# HB_main.net
KiCad netlist of a schematic drawn in Altium Designer
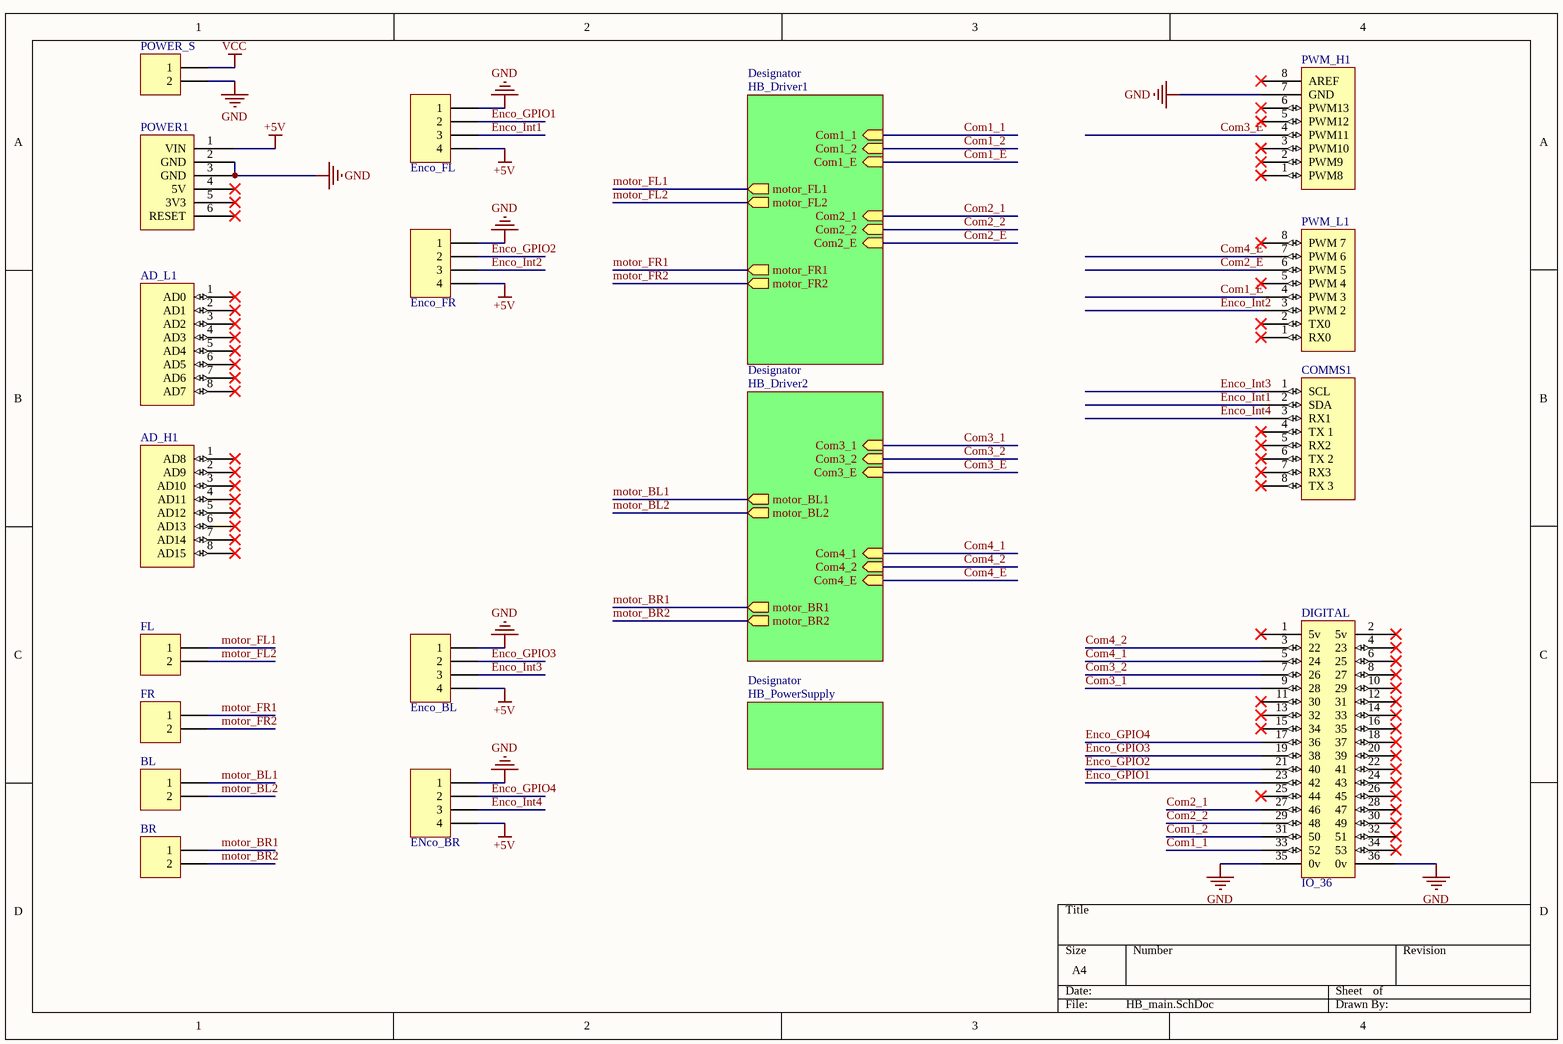
[diagram p0: HB_main.SchDoc]

(export (version "E")
  (design (tool "Eeschema 10.0.6"))
  (components
    (comp (ref "AD_H1")
      (value "AD_H")
      (footprint "Header 8x1 8.5mm")
      (description "Header, 8-Pin")
      (libsource (lib "HBLib") (part "AD_H"))
    )
    (comp (ref "AD_L1")
      (value "AD_L")
      (footprint "Header 8x1 8.5mm")
      (description "Header, 8-Pin")
      (libsource (lib "HBLib") (part "AD_L"))
    )
    (comp (ref "COMMS1")
      (value "Communication")
      (footprint "Header 8x1 8.5mm")
      (description "Header, 8-Pin")
      (libsource (lib "HBLib") (part "Communication"))
    )
    (comp (ref "DIGITAL")
      (value "IO_36")
      (footprint "HEADER 36X 8MM")
      (description "Header, 36-Pin")
      (libsource (lib "HBLib") (part "IO_36"))
    )
    (comp (ref "J3")
      (value "POWER_S")
      (footprint "Header_2")
      (description "Connecteur")
      (fields (field (name "DESIGNER") "ECAM 2005"))
      (libsource (lib "HBLib") (part "Connecteur 2"))
    )
    (comp (ref "J4")
      (value "FL")
      (footprint "Header_2")
      (description "Connecteur")
      (fields (field (name "DESIGNER") "ECAM 2005"))
      (libsource (lib "HBLib") (part "Connecteur 2"))
    )
    (comp (ref "J5")
      (value "FR")
      (footprint "Header_2")
      (description "Connecteur")
      (fields (field (name "DESIGNER") "ECAM 2005"))
      (libsource (lib "HBLib") (part "Connecteur 2"))
    )
    (comp (ref "J6")
      (value "BL")
      (footprint "Header_2")
      (description "Connecteur")
      (fields (field (name "DESIGNER") "ECAM 2005"))
      (libsource (lib "HBLib") (part "Connecteur 2"))
    )
    (comp (ref "J7")
      (value "BR")
      (footprint "Header_2")
      (description "Connecteur")
      (fields (field (name "DESIGNER") "ECAM 2005"))
      (libsource (lib "HBLib") (part "Connecteur 2"))
    )
    (comp (ref "P1")
      (value "Enco_FL")
      (footprint "MOLEX_22-27-2081")
      (description "Header, 4-Pin")
      (fields (field (name "PUBLISHER") "Altium Limited"))
      (libsource (lib "HBLib") (part "Header 4"))
    )
    (comp (ref "P2")
      (value "Enco_FR")
      (footprint "MOLEX_22-27-2081")
      (description "Header, 4-Pin")
      (fields (field (name "PUBLISHER") "Altium Limited"))
      (libsource (lib "HBLib") (part "Header 4"))
    )
    (comp (ref "P3")
      (value "Enco_BL")
      (footprint "MOLEX_22-27-2081")
      (description "Header, 4-Pin")
      (fields (field (name "PUBLISHER") "Altium Limited"))
      (libsource (lib "HBLib") (part "Header 4"))
    )
    (comp (ref "P4")
      (value "ENco_BR")
      (footprint "MOLEX_22-27-2081")
      (description "Header, 4-Pin")
      (fields (field (name "PUBLISHER") "Altium Limited"))
      (libsource (lib "HBLib") (part "Header 4"))
    )
    (comp (ref "POWER1")
      (value "POWER")
      (footprint "Header 6x1 8.5mm")
      (description "Header, 6-Pin")
      (libsource (lib "HBLib") (part "POWER"))
    )
    (comp (ref "PWM_H1")
      (value "PWM_H")
      (footprint "Header 8x1 8.5mm")
      (description "Header, 8-Pin")
      (libsource (lib "HBLib") (part "PWM_H"))
    )
    (comp (ref "PWM_L1")
      (value "PWM_L")
      (footprint "Header 8x1 8.5mm")
      (description "Header, 8-Pin")
      (libsource (lib "HBLib") (part "PWM_L"))
    )
  )
  (nets
    (net (code "1") (name "+5V") (class "Default")
      (node (ref "P1") (pin "4") (pinfunction "4_4") (pintype "passive"))
      (node (ref "P2") (pin "4") (pinfunction "4_4") (pintype "passive"))
      (node (ref "P3") (pin "4") (pinfunction "4_4") (pintype "passive"))
      (node (ref "P4") (pin "4") (pinfunction "4_4") (pintype "passive"))
      (node (ref "POWER1") (pin "1") (pinfunction "VIN_1") (pintype "power_in"))
    )
    (net (code "2") (name "/Com1_1") (class "Default")
      (node (ref "DIGITAL") (pin "33") (pinfunction "52_33") (pintype "bidirectional"))
    )
    (net (code "3") (name "/Com1_2") (class "Default")
      (node (ref "DIGITAL") (pin "31") (pinfunction "50_31") (pintype "bidirectional"))
    )
    (net (code "4") (name "/Com1_E") (class "Default")
      (node (ref "PWM_L1") (pin "4") (pinfunction "PWM_3_4") (pintype "bidirectional"))
    )
    (net (code "5") (name "/Com2_1") (class "Default")
      (node (ref "DIGITAL") (pin "27") (pinfunction "46_27") (pintype "bidirectional"))
    )
    (net (code "6") (name "/Com2_2") (class "Default")
      (node (ref "DIGITAL") (pin "29") (pinfunction "48_29") (pintype "bidirectional"))
    )
    (net (code "7") (name "/Com2_E") (class "Default")
      (node (ref "PWM_L1") (pin "6") (pinfunction "PWM_5_6") (pintype "bidirectional"))
    )
    (net (code "8") (name "/Com3_1") (class "Default")
      (node (ref "DIGITAL") (pin "9") (pinfunction "28_9") (pintype "bidirectional"))
    )
    (net (code "9") (name "/Com3_2") (class "Default")
      (node (ref "DIGITAL") (pin "7") (pinfunction "26_7") (pintype "bidirectional"))
    )
    (net (code "10") (name "/Com3_E") (class "Default")
      (node (ref "PWM_H1") (pin "4") (pinfunction "PWM11_4") (pintype "bidirectional"))
    )
    (net (code "11") (name "/Com4_1") (class "Default")
      (node (ref "DIGITAL") (pin "5") (pinfunction "24_5") (pintype "bidirectional"))
    )
    (net (code "12") (name "/Com4_2") (class "Default")
      (node (ref "DIGITAL") (pin "3") (pinfunction "22_3") (pintype "bidirectional"))
    )
    (net (code "13") (name "/Com4_E") (class "Default")
      (node (ref "PWM_L1") (pin "7") (pinfunction "PWM_6_7") (pintype "bidirectional"))
    )
    (net (code "14") (name "/Enco_GPIO1") (class "Default")
      (node (ref "DIGITAL") (pin "23") (pinfunction "42_23") (pintype "bidirectional"))
      (node (ref "P1") (pin "2") (pinfunction "2_2") (pintype "passive"))
    )
    (net (code "15") (name "/Enco_GPIO2") (class "Default")
      (node (ref "DIGITAL") (pin "21") (pinfunction "40_21") (pintype "bidirectional"))
      (node (ref "P2") (pin "2") (pinfunction "2_2") (pintype "passive"))
    )
    (net (code "16") (name "/Enco_GPIO3") (class "Default")
      (node (ref "DIGITAL") (pin "19") (pinfunction "38_19") (pintype "bidirectional"))
      (node (ref "P3") (pin "2") (pinfunction "2_2") (pintype "passive"))
    )
    (net (code "17") (name "/Enco_GPIO4") (class "Default")
      (node (ref "DIGITAL") (pin "17") (pinfunction "36_17") (pintype "bidirectional"))
      (node (ref "P4") (pin "2") (pinfunction "2_2") (pintype "passive"))
    )
    (net (code "18") (name "/Enco_Int1") (class "Default")
      (node (ref "COMMS1") (pin "2") (pinfunction "SDA_2") (pintype "bidirectional"))
      (node (ref "P1") (pin "3") (pinfunction "3_3") (pintype "passive"))
    )
    (net (code "19") (name "/Enco_Int2") (class "Default")
      (node (ref "P2") (pin "3") (pinfunction "3_3") (pintype "passive"))
      (node (ref "PWM_L1") (pin "3") (pinfunction "PWM_2_3") (pintype "bidirectional"))
    )
    (net (code "20") (name "/Enco_Int3") (class "Default")
      (node (ref "COMMS1") (pin "1") (pinfunction "SCL_1") (pintype "bidirectional"))
      (node (ref "P3") (pin "3") (pinfunction "3_3") (pintype "passive"))
    )
    (net (code "21") (name "/Enco_Int4") (class "Default")
      (node (ref "COMMS1") (pin "3") (pinfunction "RX1_3") (pintype "bidirectional"))
      (node (ref "P4") (pin "3") (pinfunction "3_3") (pintype "passive"))
    )
    (net (code "22") (name "/motor_BL1") (class "Default")
      (node (ref "J6") (pin "1") (pinfunction "1_1") (pintype "passive"))
    )
    (net (code "23") (name "/motor_BL2") (class "Default")
      (node (ref "J6") (pin "2") (pinfunction "2_2") (pintype "passive"))
    )
    (net (code "24") (name "/motor_BR1") (class "Default")
      (node (ref "J7") (pin "1") (pinfunction "1_1") (pintype "passive"))
    )
    (net (code "25") (name "/motor_BR2") (class "Default")
      (node (ref "J7") (pin "2") (pinfunction "2_2") (pintype "passive"))
    )
    (net (code "26") (name "/motor_FL1") (class "Default")
      (node (ref "J4") (pin "1") (pinfunction "1_1") (pintype "passive"))
    )
    (net (code "27") (name "/motor_FL2") (class "Default")
      (node (ref "J4") (pin "2") (pinfunction "2_2") (pintype "passive"))
    )
    (net (code "28") (name "/motor_FR1") (class "Default")
      (node (ref "J5") (pin "1") (pinfunction "1_1") (pintype "passive"))
    )
    (net (code "29") (name "/motor_FR2") (class "Default")
      (node (ref "J5") (pin "2") (pinfunction "2_2") (pintype "passive"))
    )
    (net (code "30") (name "GND") (class "Default")
      (node (ref "DIGITAL") (pin "35") (pinfunction "0v_35") (pintype "power_in"))
      (node (ref "DIGITAL") (pin "36") (pinfunction "0v_36") (pintype "power_in"))
      (node (ref "J3") (pin "2") (pinfunction "2_2") (pintype "passive"))
      (node (ref "P1") (pin "1") (pinfunction "1_1") (pintype "passive"))
      (node (ref "P2") (pin "1") (pinfunction "1_1") (pintype "passive"))
      (node (ref "P3") (pin "1") (pinfunction "1_1") (pintype "passive"))
      (node (ref "P4") (pin "1") (pinfunction "1_1") (pintype "passive"))
      (node (ref "POWER1") (pin "2") (pinfunction "GND_2") (pintype "power_in"))
      (node (ref "POWER1") (pin "3") (pinfunction "GND_3") (pintype "power_in"))
      (node (ref "PWM_H1") (pin "7") (pinfunction "GND_7") (pintype "power_in"))
    )
    (net (code "31") (name "VCC") (class "Default")
      (node (ref "J3") (pin "1") (pinfunction "1_1") (pintype "passive"))
    )
    (net (code "32") (name "unconnected-(AD_H1-AD8-Pad1)") (class "Default")
      (node (ref "AD_H1") (pin "1") (pinfunction "AD8_1") (pintype "bidirectional+no_connect"))
    )
    (net (code "33") (name "unconnected-(AD_H1-AD9-Pad2)") (class "Default")
      (node (ref "AD_H1") (pin "2") (pinfunction "AD9_2") (pintype "bidirectional+no_connect"))
    )
    (net (code "34") (name "unconnected-(AD_H1-AD10-Pad3)") (class "Default")
      (node (ref "AD_H1") (pin "3") (pinfunction "AD10_3") (pintype "bidirectional+no_connect"))
    )
    (net (code "35") (name "unconnected-(AD_H1-AD11-Pad4)") (class "Default")
      (node (ref "AD_H1") (pin "4") (pinfunction "AD11_4") (pintype "bidirectional+no_connect"))
    )
    (net (code "36") (name "unconnected-(AD_H1-AD12-Pad5)") (class "Default")
      (node (ref "AD_H1") (pin "5") (pinfunction "AD12_5") (pintype "bidirectional+no_connect"))
    )
    (net (code "37") (name "unconnected-(AD_H1-AD13-Pad6)") (class "Default")
      (node (ref "AD_H1") (pin "6") (pinfunction "AD13_6") (pintype "bidirectional+no_connect"))
    )
    (net (code "38") (name "unconnected-(AD_H1-AD14-Pad7)") (class "Default")
      (node (ref "AD_H1") (pin "7") (pinfunction "AD14_7") (pintype "bidirectional+no_connect"))
    )
    (net (code "39") (name "unconnected-(AD_H1-AD15-Pad8)") (class "Default")
      (node (ref "AD_H1") (pin "8") (pinfunction "AD15_8") (pintype "bidirectional+no_connect"))
    )
    (net (code "40") (name "unconnected-(AD_L1-AD0-Pad1)") (class "Default")
      (node (ref "AD_L1") (pin "1") (pinfunction "AD0_1") (pintype "bidirectional+no_connect"))
    )
    (net (code "41") (name "unconnected-(AD_L1-AD1-Pad2)") (class "Default")
      (node (ref "AD_L1") (pin "2") (pinfunction "AD1_2") (pintype "bidirectional+no_connect"))
    )
    (net (code "42") (name "unconnected-(AD_L1-AD2-Pad3)") (class "Default")
      (node (ref "AD_L1") (pin "3") (pinfunction "AD2_3") (pintype "bidirectional+no_connect"))
    )
    (net (code "43") (name "unconnected-(AD_L1-AD3-Pad4)") (class "Default")
      (node (ref "AD_L1") (pin "4") (pinfunction "AD3_4") (pintype "bidirectional+no_connect"))
    )
    (net (code "44") (name "unconnected-(AD_L1-AD4-Pad5)") (class "Default")
      (node (ref "AD_L1") (pin "5") (pinfunction "AD4_5") (pintype "bidirectional+no_connect"))
    )
    (net (code "45") (name "unconnected-(AD_L1-AD5-Pad6)") (class "Default")
      (node (ref "AD_L1") (pin "6") (pinfunction "AD5_6") (pintype "bidirectional+no_connect"))
    )
    (net (code "46") (name "unconnected-(AD_L1-AD6-Pad7)") (class "Default")
      (node (ref "AD_L1") (pin "7") (pinfunction "AD6_7") (pintype "bidirectional+no_connect"))
    )
    (net (code "47") (name "unconnected-(AD_L1-AD7-Pad8)") (class "Default")
      (node (ref "AD_L1") (pin "8") (pinfunction "AD7_8") (pintype "bidirectional+no_connect"))
    )
    (net (code "48") (name "unconnected-(COMMS1-RX2-Pad5)") (class "Default")
      (node (ref "COMMS1") (pin "5") (pinfunction "RX2_5") (pintype "bidirectional+no_connect"))
    )
    (net (code "49") (name "unconnected-(COMMS1-RX3-Pad7)") (class "Default")
      (node (ref "COMMS1") (pin "7") (pinfunction "RX3_7") (pintype "bidirectional+no_connect"))
    )
    (net (code "50") (name "unconnected-(COMMS1-TX_1-Pad4)") (class "Default")
      (node (ref "COMMS1") (pin "4") (pinfunction "TX_1_4") (pintype "bidirectional+no_connect"))
    )
    (net (code "51") (name "unconnected-(COMMS1-TX_2-Pad6)") (class "Default")
      (node (ref "COMMS1") (pin "6") (pinfunction "TX_2_6") (pintype "bidirectional+no_connect"))
    )
    (net (code "52") (name "unconnected-(COMMS1-TX_3-Pad8)") (class "Default")
      (node (ref "COMMS1") (pin "8") (pinfunction "TX_3_8") (pintype "bidirectional+no_connect"))
    )
    (net (code "53") (name "unconnected-(DIGITAL-5v-Pad1)") (class "Default")
      (node (ref "DIGITAL") (pin "1") (pinfunction "5v_1") (pintype "power_in+no_connect"))
    )
    (net (code "54") (name "unconnected-(DIGITAL-5v-Pad2)") (class "Default")
      (node (ref "DIGITAL") (pin "2") (pinfunction "5v_2") (pintype "power_in+no_connect"))
    )
    (net (code "55") (name "unconnected-(DIGITAL-23-Pad4)") (class "Default")
      (node (ref "DIGITAL") (pin "4") (pinfunction "23_4") (pintype "bidirectional+no_connect"))
    )
    (net (code "56") (name "unconnected-(DIGITAL-25-Pad6)") (class "Default")
      (node (ref "DIGITAL") (pin "6") (pinfunction "25_6") (pintype "bidirectional+no_connect"))
    )
    (net (code "57") (name "unconnected-(DIGITAL-27-Pad8)") (class "Default")
      (node (ref "DIGITAL") (pin "8") (pinfunction "27_8") (pintype "bidirectional+no_connect"))
    )
    (net (code "58") (name "unconnected-(DIGITAL-29-Pad10)") (class "Default")
      (node (ref "DIGITAL") (pin "10") (pinfunction "29_10") (pintype "bidirectional+no_connect"))
    )
    (net (code "59") (name "unconnected-(DIGITAL-30-Pad11)") (class "Default")
      (node (ref "DIGITAL") (pin "11") (pinfunction "30_11") (pintype "bidirectional+no_connect"))
    )
    (net (code "60") (name "unconnected-(DIGITAL-31-Pad12)") (class "Default")
      (node (ref "DIGITAL") (pin "12") (pinfunction "31_12") (pintype "bidirectional+no_connect"))
    )
    (net (code "61") (name "unconnected-(DIGITAL-32-Pad13)") (class "Default")
      (node (ref "DIGITAL") (pin "13") (pinfunction "32_13") (pintype "bidirectional+no_connect"))
    )
    (net (code "62") (name "unconnected-(DIGITAL-33-Pad14)") (class "Default")
      (node (ref "DIGITAL") (pin "14") (pinfunction "33_14") (pintype "bidirectional+no_connect"))
    )
    (net (code "63") (name "unconnected-(DIGITAL-34-Pad15)") (class "Default")
      (node (ref "DIGITAL") (pin "15") (pinfunction "34_15") (pintype "bidirectional+no_connect"))
    )
    (net (code "64") (name "unconnected-(DIGITAL-35-Pad16)") (class "Default")
      (node (ref "DIGITAL") (pin "16") (pinfunction "35_16") (pintype "bidirectional+no_connect"))
    )
    (net (code "65") (name "unconnected-(DIGITAL-37-Pad18)") (class "Default")
      (node (ref "DIGITAL") (pin "18") (pinfunction "37_18") (pintype "bidirectional+no_connect"))
    )
    (net (code "66") (name "unconnected-(DIGITAL-39-Pad20)") (class "Default")
      (node (ref "DIGITAL") (pin "20") (pinfunction "39_20") (pintype "bidirectional+no_connect"))
    )
    (net (code "67") (name "unconnected-(DIGITAL-41-Pad22)") (class "Default")
      (node (ref "DIGITAL") (pin "22") (pinfunction "41_22") (pintype "bidirectional+no_connect"))
    )
    (net (code "68") (name "unconnected-(DIGITAL-43-Pad24)") (class "Default")
      (node (ref "DIGITAL") (pin "24") (pinfunction "43_24") (pintype "bidirectional+no_connect"))
    )
    (net (code "69") (name "unconnected-(DIGITAL-44-Pad25)") (class "Default")
      (node (ref "DIGITAL") (pin "25") (pinfunction "44_25") (pintype "bidirectional+no_connect"))
    )
    (net (code "70") (name "unconnected-(DIGITAL-45-Pad26)") (class "Default")
      (node (ref "DIGITAL") (pin "26") (pinfunction "45_26") (pintype "bidirectional+no_connect"))
    )
    (net (code "71") (name "unconnected-(DIGITAL-47-Pad28)") (class "Default")
      (node (ref "DIGITAL") (pin "28") (pinfunction "47_28") (pintype "bidirectional+no_connect"))
    )
    (net (code "72") (name "unconnected-(DIGITAL-49-Pad30)") (class "Default")
      (node (ref "DIGITAL") (pin "30") (pinfunction "49_30") (pintype "bidirectional+no_connect"))
    )
    (net (code "73") (name "unconnected-(DIGITAL-51-Pad32)") (class "Default")
      (node (ref "DIGITAL") (pin "32") (pinfunction "51_32") (pintype "bidirectional+no_connect"))
    )
    (net (code "74") (name "unconnected-(DIGITAL-53-Pad34)") (class "Default")
      (node (ref "DIGITAL") (pin "34") (pinfunction "53_34") (pintype "bidirectional+no_connect"))
    )
    (net (code "75") (name "unconnected-(POWER1-3V3-Pad5)") (class "Default")
      (node (ref "POWER1") (pin "5") (pinfunction "3V3_5") (pintype "power_in+no_connect"))
    )
    (net (code "76") (name "unconnected-(POWER1-5V-Pad4)") (class "Default")
      (node (ref "POWER1") (pin "4") (pinfunction "5V_4") (pintype "power_in+no_connect"))
    )
    (net (code "77") (name "unconnected-(POWER1-RESET-Pad6)") (class "Default")
      (node (ref "POWER1") (pin "6") (pinfunction "RESET_6") (pintype "passive+no_connect"))
    )
    (net (code "78") (name "unconnected-(PWM_H1-AREF-Pad8)") (class "Default")
      (node (ref "PWM_H1") (pin "8") (pinfunction "AREF_8") (pintype "passive+no_connect"))
    )
    (net (code "79") (name "unconnected-(PWM_H1-PWM8-Pad1)") (class "Default")
      (node (ref "PWM_H1") (pin "1") (pinfunction "PWM8_1") (pintype "bidirectional+no_connect"))
    )
    (net (code "80") (name "unconnected-(PWM_H1-PWM9-Pad2)") (class "Default")
      (node (ref "PWM_H1") (pin "2") (pinfunction "PWM9_2") (pintype "bidirectional+no_connect"))
    )
    (net (code "81") (name "unconnected-(PWM_H1-PWM10-Pad3)") (class "Default")
      (node (ref "PWM_H1") (pin "3") (pinfunction "PWM10_3") (pintype "bidirectional+no_connect"))
    )
    (net (code "82") (name "unconnected-(PWM_H1-PWM12-Pad5)") (class "Default")
      (node (ref "PWM_H1") (pin "5") (pinfunction "PWM12_5") (pintype "bidirectional+no_connect"))
    )
    (net (code "83") (name "unconnected-(PWM_H1-PWM13-Pad6)") (class "Default")
      (node (ref "PWM_H1") (pin "6") (pinfunction "PWM13_6") (pintype "bidirectional+no_connect"))
    )
    (net (code "84") (name "unconnected-(PWM_L1-PWM_4-Pad5)") (class "Default")
      (node (ref "PWM_L1") (pin "5") (pinfunction "PWM_4_5") (pintype "bidirectional+no_connect"))
    )
    (net (code "85") (name "unconnected-(PWM_L1-PWM_7-Pad8)") (class "Default")
      (node (ref "PWM_L1") (pin "8") (pinfunction "PWM_7_8") (pintype "bidirectional+no_connect"))
    )
    (net (code "86") (name "unconnected-(PWM_L1-RX0-Pad1)") (class "Default")
      (node (ref "PWM_L1") (pin "1") (pinfunction "RX0_1") (pintype "bidirectional+no_connect"))
    )
    (net (code "87") (name "unconnected-(PWM_L1-TX0-Pad2)") (class "Default")
      (node (ref "PWM_L1") (pin "2") (pinfunction "TX0_2") (pintype "bidirectional+no_connect"))
    )
  )
)
